# resonant-bp.net
KiCad netlist of a schematic drawn in EAGLE
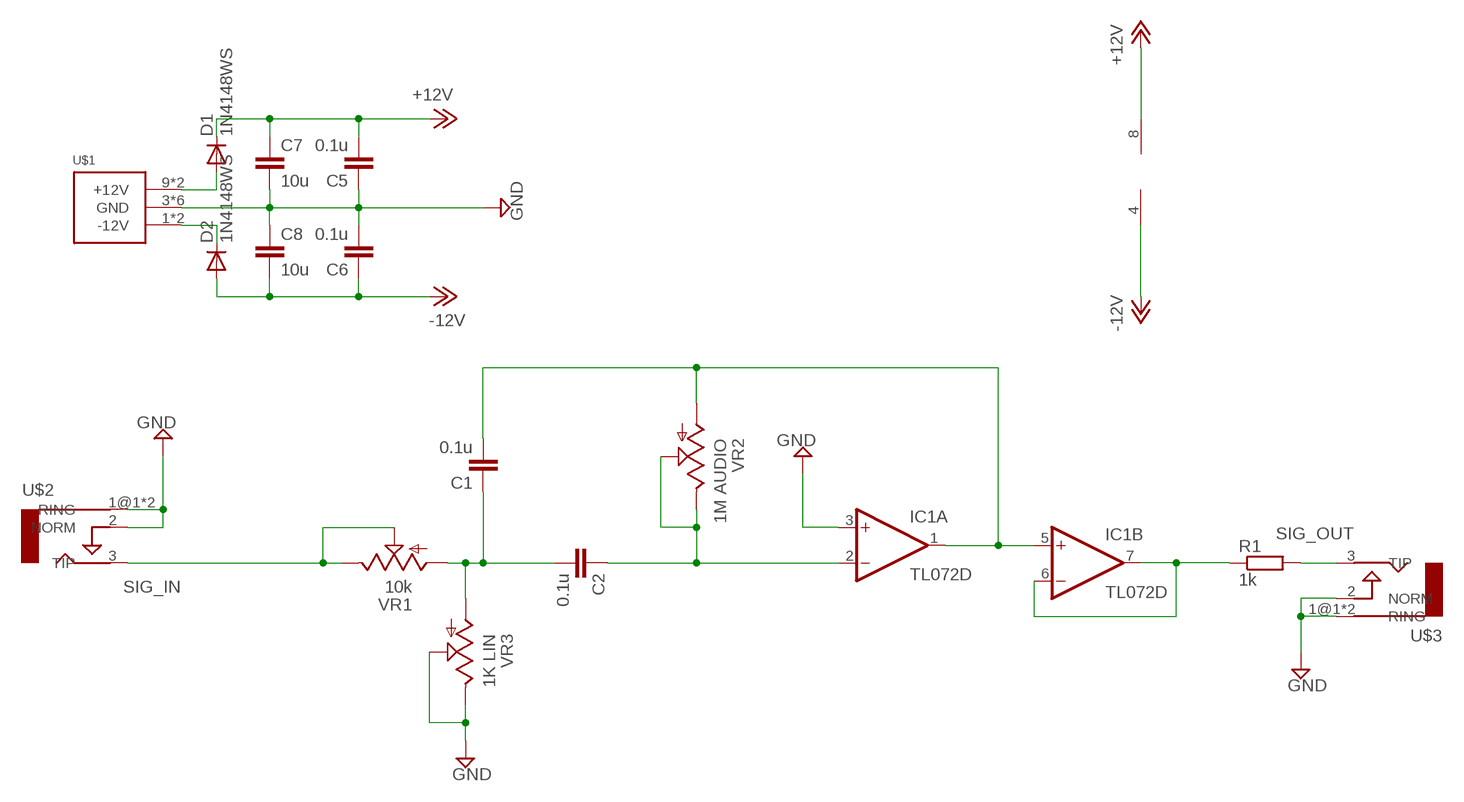
[diagram p0: schematic, sheet 1]

(export (version "E")
  (design (tool "Eeschema 10.0.6"))
  (components
    (comp (ref "C1")
      (value "0.1u")
      (footprint "eagle-import:C0805")
      (libsource (lib "eagle-import") (part "C-EUC0805"))
    )
    (comp (ref "C2")
      (value "0.1u")
      (footprint "eagle-import:C0805")
      (libsource (lib "eagle-import") (part "C-EUC0805"))
    )
    (comp (ref "C5")
      (value "0.1u")
      (footprint "eagle-import:C0805")
      (libsource (lib "eagle-import") (part "C-EUC0805"))
    )
    (comp (ref "C6")
      (value "0.1u")
      (footprint "eagle-import:C0805")
      (libsource (lib "eagle-import") (part "C-EUC0805"))
    )
    (comp (ref "C7")
      (value "10u")
      (footprint "eagle-import:C0805")
      (libsource (lib "eagle-import") (part "C-EUC0805"))
    )
    (comp (ref "C8")
      (value "10u")
      (footprint "eagle-import:C0805")
      (libsource (lib "eagle-import") (part "C-EUC0805"))
    )
    (comp (ref "D1")
      (value "1N4148WS")
      (footprint "eagle-import:SOD323-W")
      (libsource (lib "eagle-import") (part "DIODE-SOD323-W"))
    )
    (comp (ref "D2")
      (value "1N4148WS")
      (footprint "eagle-import:SOD323-W")
      (libsource (lib "eagle-import") (part "DIODE-SOD323-W"))
    )
    (comp (ref "IC1")
      (value "TL072D")
      (footprint "eagle-import:SO08")
      (libsource (lib "eagle-import") (part "TL072D"))
    )
    (comp (ref "R1")
      (value "1k")
      (footprint "eagle-import:R0805")
      (libsource (lib "eagle-import") (part "R-EU_R0805"))
    )
    (comp (ref "U$1")
      (value "POWER_SIMPLE10")
      (footprint "eagle-import:POWER_10")
      (libsource (lib "eagle-import") (part "POWER_SIMPLE10"))
    )
    (comp (ref "U$2")
      (value "AUDIO-JACKERTHENVAR")
      (footprint "eagle-import:ERTHENVAR-JACK")
      (libsource (lib "eagle-import") (part "AUDIO-JACKERTHENVAR"))
    )
    (comp (ref "U$3")
      (value "AUDIO-JACKERTHENVAR")
      (footprint "eagle-import:ERTHENVAR-JACK")
      (libsource (lib "eagle-import") (part "AUDIO-JACKERTHENVAR"))
    )
    (comp (ref "VR1")
      (value "10k")
      (footprint "eagle-import:9MM_SNAP-IN_POT")
      (libsource (lib "eagle-import") (part "9MM_SNAP-IN_POT_"))
    )
    (comp (ref "VR2")
      (value "1M AUDIO")
      (footprint "eagle-import:9MM_SNAP-IN_POT")
      (libsource (lib "eagle-import") (part "9MM_SNAP-IN_POT_"))
    )
    (comp (ref "VR3")
      (value "1K LIN")
      (footprint "eagle-import:9MM_SNAP-IN_POT")
      (libsource (lib "eagle-import") (part "9MM_SNAP-IN_POT_"))
    )
  )
  (nets
    (net (code "1") (name "+12V") (class "Default")
      (node (ref "C5") (pin "2") (pinfunction "2_2") (pintype "passive"))
      (node (ref "C7") (pin "1") (pinfunction "1_1") (pintype "passive"))
      (node (ref "D1") (pin "C") (pinfunction "C_C") (pintype "passive"))
      (node (ref "IC1") (pin "8") (pinfunction "V+_8") (pintype "power_in"))
    )
    (net (code "2") (name "-12V") (class "Default")
      (node (ref "C6") (pin "1") (pinfunction "1_1") (pintype "passive"))
      (node (ref "C8") (pin "2") (pinfunction "2_2") (pintype "passive"))
      (node (ref "D2") (pin "A") (pinfunction "A_A") (pintype "passive"))
      (node (ref "IC1") (pin "4") (pinfunction "V-_4") (pintype "power_in"))
    )
    (net (code "3") (name "/SIG_IN") (class "Default")
      (node (ref "U$2") (pin "3") (pinfunction "TIP_3") (pintype "bidirectional"))
      (node (ref "VR1") (pin "2") (pinfunction "S_2") (pintype "passive"))
      (node (ref "VR1") (pin "3") (pinfunction "E_3") (pintype "passive"))
    )
    (net (code "4") (name "/SIG_OUT") (class "Default")
      (node (ref "R1") (pin "2") (pinfunction "2_2") (pintype "passive"))
      (node (ref "U$3") (pin "3") (pinfunction "TIP_3") (pintype "bidirectional"))
    )
    (net (code "5") (name "GND") (class "Default")
      (node (ref "C5") (pin "1") (pinfunction "1_1") (pintype "passive"))
      (node (ref "C6") (pin "2") (pinfunction "2_2") (pintype "passive"))
      (node (ref "C7") (pin "2") (pinfunction "2_2") (pintype "passive"))
      (node (ref "C8") (pin "1") (pinfunction "1_1") (pintype "passive"))
      (node (ref "IC1") (pin "3") (pinfunction "+IN_3") (pintype "input"))
      (node (ref "U$1") (pin "3") (pinfunction "GND_3") (pintype "bidirectional"))
      (node (ref "U$1") (pin "4") (pinfunction "GND_4") (pintype "bidirectional"))
      (node (ref "U$1") (pin "5") (pinfunction "GND_5") (pintype "bidirectional"))
      (node (ref "U$1") (pin "6") (pinfunction "GND_6") (pintype "bidirectional"))
      (node (ref "U$1") (pin "7") (pinfunction "GND_7") (pintype "bidirectional"))
      (node (ref "U$1") (pin "8") (pinfunction "GND_8") (pintype "bidirectional"))
      (node (ref "U$2") (pin "1@1") (pinfunction "RING_1@1") (pintype "bidirectional"))
      (node (ref "U$2") (pin "1@2") (pinfunction "RING_1@2") (pintype "bidirectional"))
      (node (ref "U$2") (pin "2") (pinfunction "NORM_2") (pintype "bidirectional"))
      (node (ref "U$3") (pin "1@1") (pinfunction "RING_1@1") (pintype "bidirectional"))
      (node (ref "U$3") (pin "1@2") (pinfunction "RING_1@2") (pintype "bidirectional"))
      (node (ref "U$3") (pin "2") (pinfunction "NORM_2") (pintype "bidirectional"))
      (node (ref "VR3") (pin "2") (pinfunction "S_2") (pintype "passive"))
      (node (ref "VR3") (pin "3") (pinfunction "E_3") (pintype "passive"))
    )
    (net (code "6") (name "Net-(D1-PadA)") (class "Default")
      (node (ref "D1") (pin "A") (pinfunction "A_A") (pintype "passive"))
      (node (ref "U$1") (pin "10") (pinfunction "+12V_10") (pintype "bidirectional"))
      (node (ref "U$1") (pin "9") (pinfunction "+12V_9") (pintype "bidirectional"))
    )
    (net (code "7") (name "Net-(D2-PadC)") (class "Default")
      (node (ref "D2") (pin "C") (pinfunction "C_C") (pintype "passive"))
      (node (ref "U$1") (pin "1") (pinfunction "-12V_1") (pintype "bidirectional"))
      (node (ref "U$1") (pin "2") (pinfunction "-12V_2") (pintype "bidirectional"))
    )
    (net (code "8") (name "Net-(IC1A--IN)") (class "Default")
      (node (ref "C2") (pin "1") (pinfunction "1_1") (pintype "passive"))
      (node (ref "IC1") (pin "2") (pinfunction "-IN_2") (pintype "input"))
      (node (ref "VR2") (pin "2") (pinfunction "S_2") (pintype "passive"))
      (node (ref "VR2") (pin "3") (pinfunction "E_3") (pintype "passive"))
    )
    (net (code "9") (name "Net-(IC1A-OUT)") (class "Default")
      (node (ref "C1") (pin "2") (pinfunction "2_2") (pintype "passive"))
      (node (ref "IC1") (pin "1") (pinfunction "OUT_1") (pintype "output"))
      (node (ref "IC1") (pin "5") (pinfunction "+IN_5") (pintype "input"))
      (node (ref "VR2") (pin "1") (pinfunction "A_1") (pintype "passive"))
    )
    (net (code "10") (name "Net-(IC1B--IN)") (class "Default")
      (node (ref "IC1") (pin "6") (pinfunction "-IN_6") (pintype "input"))
      (node (ref "IC1") (pin "7") (pinfunction "OUT_7") (pintype "output"))
      (node (ref "R1") (pin "1") (pinfunction "1_1") (pintype "passive"))
    )
    (net (code "11") (name "Net-(VR1-A)") (class "Default")
      (node (ref "C1") (pin "1") (pinfunction "1_1") (pintype "passive"))
      (node (ref "C2") (pin "2") (pinfunction "2_2") (pintype "passive"))
      (node (ref "VR1") (pin "1") (pinfunction "A_1") (pintype "passive"))
      (node (ref "VR3") (pin "1") (pinfunction "A_1") (pintype "passive"))
    )
  )
)
